# GSM.net
KiCad netlist of a schematic drawn in Altium Designer
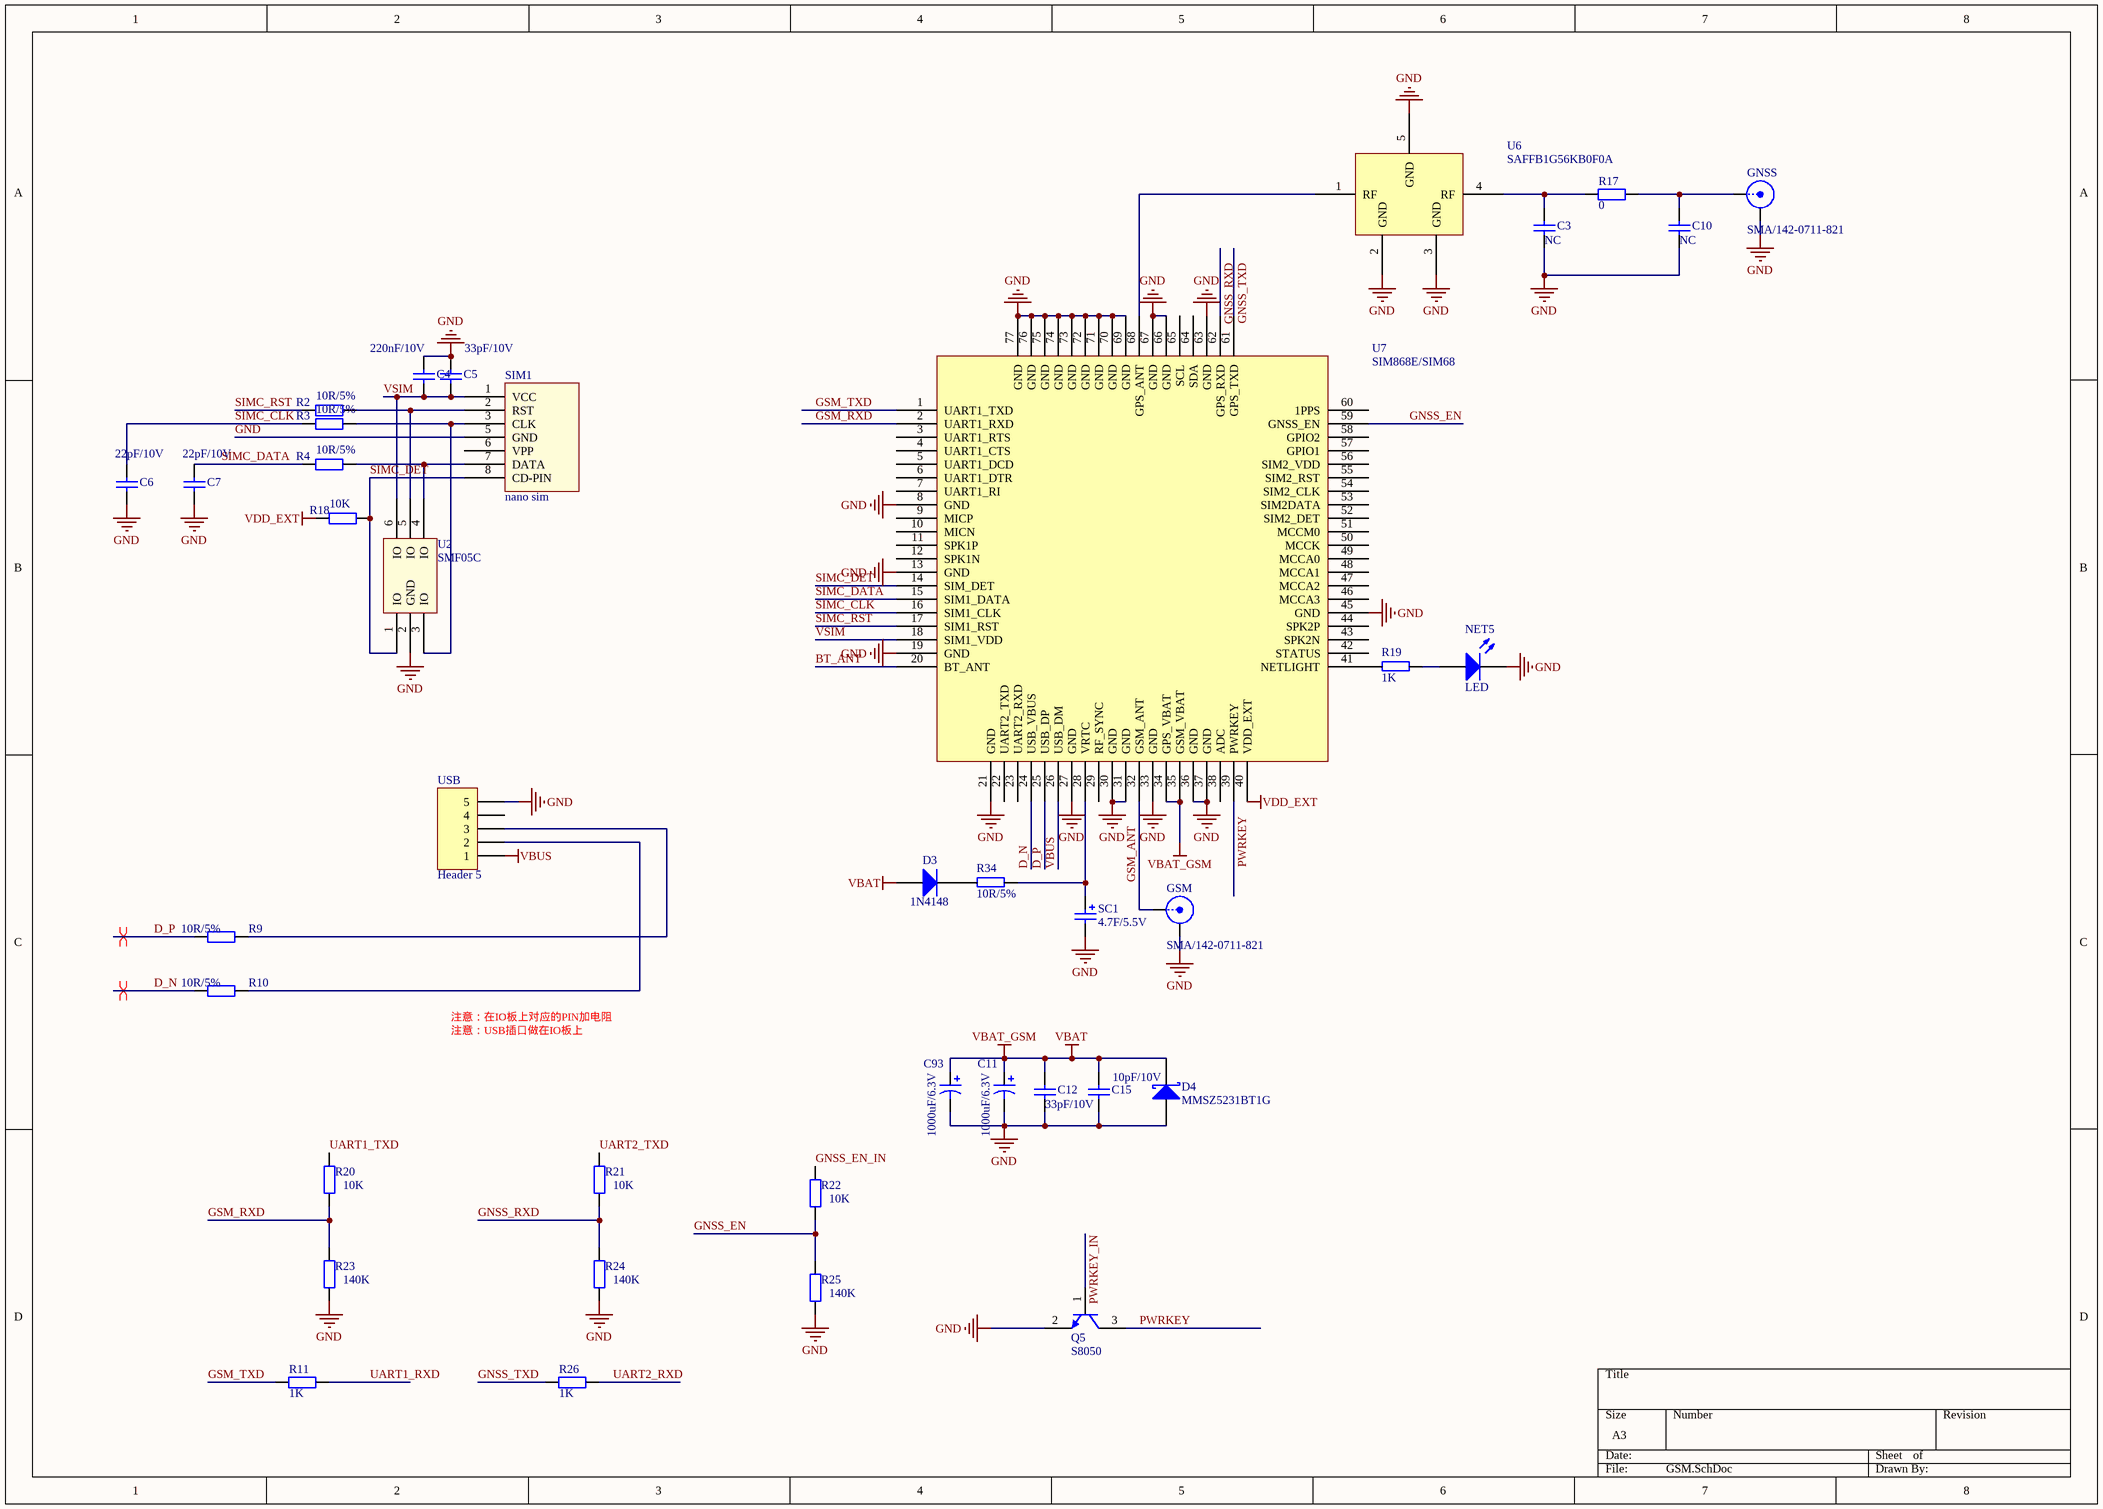
[diagram p0: GSM.SchDoc]

(export (version "E")
  (design (tool "Eeschema 10.0.6"))
  (components
    (comp (ref "C3")
      (value "NC")
      (footprint "0603C")
      (description "Capacitor")
      (fields (field (name "PUBLISHER") "Altium Limited"))
      (libsource (lib "Miscellaneous Devices") (part "Cap"))
    )
    (comp (ref "C4")
      (value "220nF/10V")
      (footprint "0603C")
      (description "Capacitor")
      (fields (field (name "PUBLISHER") "Altium Limited"))
      (libsource (lib "Miscellaneous Devices") (part "Cap"))
    )
    (comp (ref "C5")
      (value "33pF/10V")
      (footprint "0603C")
      (description "Capacitor")
      (fields (field (name "PUBLISHER") "Altium Limited"))
      (libsource (lib "Miscellaneous Devices") (part "Cap"))
    )
    (comp (ref "C6")
      (value "22pF/10V")
      (footprint "0603C")
      (description "Capacitor")
      (fields (field (name "PUBLISHER") "Altium Limited"))
      (libsource (lib "Miscellaneous Devices") (part "Cap"))
    )
    (comp (ref "C7")
      (value "22pF/10V")
      (footprint "0603C")
      (description "Capacitor")
      (fields (field (name "PUBLISHER") "Altium Limited"))
      (libsource (lib "Miscellaneous Devices") (part "Cap"))
    )
    (comp (ref "C10")
      (value "NC")
      (footprint "0603C")
      (description "Capacitor")
      (fields (field (name "PUBLISHER") "Altium Limited"))
      (libsource (lib "Miscellaneous Devices") (part "Cap"))
    )
    (comp (ref "C11")
      (value "1000uF/6.3V")
      (footprint "7343")
      (description "Polarized Capacitor (Radial)")
      (fields (field (name "PUBLISHER") "Altium Limited"))
      (libsource (lib "Miscellaneous Devices") (part "Cap Pol1"))
    )
    (comp (ref "C12")
      (value "33pF/10V")
      (footprint "0603C")
      (description "Capacitor")
      (fields (field (name "PUBLISHER") "Altium Limited"))
      (libsource (lib "Miscellaneous Devices") (part "Cap"))
    )
    (comp (ref "C15")
      (value "10pF/10V")
      (footprint "0603C")
      (description "Capacitor")
      (fields (field (name "PUBLISHER") "Altium Limited"))
      (libsource (lib "Miscellaneous Devices") (part "Cap"))
    )
    (comp (ref "C93")
      (value "1000uF/6.3V")
      (footprint "7343")
      (description "Polarized Capacitor (Radial)")
      (fields (field (name "PUBLISHER") "Altium Limited"))
      (libsource (lib "Miscellaneous Devices") (part "Cap Pol1"))
    )
    (comp (ref "D3")
      (value "1N4148")
      (footprint "LL34")
      (description "High Conductance Fast Diode")
      (fields (field (name "PUBLISHER") "Altium Limited"))
      (libsource (lib "Miscellaneous Devices") (part "Diode 1N4148"))
    )
    (comp (ref "D4")
      (value "MMSZ5231BT1G")
      (footprint "SOD123")
      (description "Schottky Rectifier")
      (fields (field (name "PUBLISHER") "Altium Limited"))
      (libsource (lib "Miscellaneous Devices") (part "Diode 10TQ040"))
    )
    (comp (ref "GNSS")
      (value "SMA/142-0711-821")
      (footprint "SMA END LAUNCH JACK RECEPTACLE SHORT")
      (description "SMA Straight Connector")
      (fields (field (name "PUBLISHER") "Altium Limited"))
      (libsource (lib "SX1276_e266v02a") (part "SMA"))
    )
    (comp (ref "GSM")
      (value "SMA/142-0711-821")
      (footprint "SMA END LAUNCH JACK RECEPTACLE SHORT")
      (description "SMA Straight Connector")
      (fields (field (name "PUBLISHER") "Altium Limited"))
      (libsource (lib "SX1276_e266v02a") (part "SMA"))
    )
    (comp (ref "NET5")
      (value "LED")
      (footprint "0603LED")
      (description "Typical RED, GREEN, YELLOW, AMBER GaAs LED")
      (fields (field (name "PUBLISHER") "Altium Limited"))
      (libsource (lib "SIM800C 原理图库") (part "LED2"))
    )
    (comp (ref "Q5") (value "S8050") (footprint "SOT23-3") (libsource (lib "Schlib1") (part "NPN")))
    (comp (ref "R2")
      (value "10R/5%")
      (footprint "0603R")
      (description "Resistor")
      (fields (field (name "PUBLISHER") "Altium Limited"))
      (libsource (lib "") (part "Res2_1"))
    )
    (comp (ref "R3")
      (value "10R/5%")
      (footprint "0603R")
      (description "Resistor")
      (fields (field (name "PUBLISHER") "Altium Limited"))
      (libsource (lib "") (part "Res2_1"))
    )
    (comp (ref "R4")
      (value "10R/5%")
      (footprint "0603R")
      (description "Resistor")
      (fields (field (name "PUBLISHER") "Altium Limited"))
      (libsource (lib "") (part "Res2_1"))
    )
    (comp (ref "R9")
      (value "10R/5%")
      (footprint "0603R")
      (description "Resistor SMD - IEC symbol version")
      (libsource (lib "SX1276_e266v02a") (part "Resistor"))
    )
    (comp (ref "R10")
      (value "10R/5%")
      (footprint "0603R")
      (description "Resistor SMD - IEC symbol version")
      (libsource (lib "SX1276_e266v02a") (part "Resistor"))
    )
    (comp (ref "R11")
      (value "1K")
      (footprint "0603R")
      (description "Resistor")
      (fields (field (name "PUBLISHER") "Altium Limited"))
      (libsource (lib "") (part "Res2_2"))
    )
    (comp (ref "R17")
      (value "0")
      (footprint "0603R")
      (description "Resistor")
      (fields (field (name "PUBLISHER") "Altium Limited"))
      (libsource (lib "") (part "Res2_2"))
    )
    (comp (ref "R18")
      (value "10K")
      (footprint "0603R")
      (description "Resistor")
      (fields (field (name "PUBLISHER") "Altium Limited"))
      (libsource (lib "") (part "Res2_1"))
    )
    (comp (ref "R19") (value "1K") (footprint "0603r") (libsource (lib "SIM800C 原理图库") (part "R")))
    (comp (ref "R20")
      (value "10K")
      (footprint "0603R")
      (description "Resistor")
      (fields (field (name "PUBLISHER") "Altium Limited"))
      (libsource (lib "Miscellaneous Devices") (part "Res2"))
    )
    (comp (ref "R21")
      (value "10K")
      (footprint "0603R")
      (description "Resistor")
      (fields (field (name "PUBLISHER") "Altium Limited"))
      (libsource (lib "Miscellaneous Devices") (part "Res2"))
    )
    (comp (ref "R22")
      (value "10K")
      (footprint "0603R")
      (description "Resistor")
      (fields (field (name "PUBLISHER") "Altium Limited"))
      (libsource (lib "Miscellaneous Devices") (part "Res2"))
    )
    (comp (ref "R23")
      (value "140K")
      (footprint "0603R")
      (description "Resistor")
      (fields (field (name "PUBLISHER") "Altium Limited"))
      (libsource (lib "Miscellaneous Devices") (part "Res2"))
    )
    (comp (ref "R24")
      (value "140K")
      (footprint "0603R")
      (description "Resistor")
      (fields (field (name "PUBLISHER") "Altium Limited"))
      (libsource (lib "Miscellaneous Devices") (part "Res2"))
    )
    (comp (ref "R25")
      (value "140K")
      (footprint "0603R")
      (description "Resistor")
      (fields (field (name "PUBLISHER") "Altium Limited"))
      (libsource (lib "Miscellaneous Devices") (part "Res2"))
    )
    (comp (ref "R26")
      (value "1K")
      (footprint "0603R")
      (description "Resistor")
      (fields (field (name "PUBLISHER") "Altium Limited"))
      (libsource (lib "") (part "Res2_2"))
    )
    (comp (ref "R34") (value "10R/5%") (footprint "0603r") (libsource (lib "SIM800C 原理图库") (part "R")))
    (comp (ref "SC1")
      (value "4.7F/5.5V")
      (footprint "SF-13.5*6.5")
      (description "Polarized Capacitor (Axial)")
      (fields (field (name "PUBLISHER") "Altium Limited"))
      (libsource (lib "Miscellaneous Devices") (part "Cap Pol2"))
    )
    (comp (ref "SIM1") (value "nano sim") (footprint "Nano SIM") (libsource (lib "lm") (part "nano sim")))
    (comp (ref "U2") (value "SMF05C") (footprint "SC70-6L") (libsource (lib "lm") (part "SMF05C")))
    (comp (ref "U6")
      (value "SAFFB1G56KB0F0A")
      (footprint "SAFFB1G56KB0F0A")
      (libsource (lib "stm32") (part "SAFFB1G56KBOFA"))
    )
    (comp (ref "U7")
      (value "SIM868E/SIM68")
      (footprint "SIM868")
      (libsource (lib "stm32") (part "SIM868E/SIM868"))
    )
    (comp (ref "USB")
      (value "Header 5")
      (footprint "Micro_USB_PH")
      (description "Header, 5-Pin")
      (fields (field (name "PUBLISHER") "Altium Limited"))
      (libsource (lib "Miscellaneous Connectors") (part "Header 5"))
    )
  )
  (nets
    (net (code "1") (name "/BT_ANT") (class "Default")
      (node (ref "U7") (pin "20") (pinfunction "BT_ANT_20") (pintype "passive"))
    )
    (net (code "2") (name "/D_N") (class "Default")
      (node (ref "R10") (pin "1") (pinfunction "1_1") (pintype "passive"))
      (node (ref "U7") (pin "24") (pinfunction "USB_VBUS_24") (pintype "passive"))
    )
    (net (code "3") (name "/D_P") (class "Default")
      (node (ref "R9") (pin "1") (pinfunction "1_1") (pintype "passive"))
      (node (ref "U7") (pin "25") (pinfunction "USB_DP_25") (pintype "passive"))
    )
    (net (code "4") (name "/GNSS_EN") (class "Default")
      (node (ref "R22") (pin "2") (pinfunction "2_2") (pintype "passive"))
      (node (ref "R25") (pin "1") (pinfunction "1_1") (pintype "passive"))
      (node (ref "U7") (pin "59") (pinfunction "GNSS_EN_59") (pintype "passive"))
    )
    (net (code "5") (name "/GNSS_EN_IN") (class "Default")
      (node (ref "R22") (pin "1") (pinfunction "1_1") (pintype "passive"))
    )
    (net (code "6") (name "/GNSS_RXD") (class "Default")
      (node (ref "R21") (pin "2") (pinfunction "2_2") (pintype "passive"))
      (node (ref "R24") (pin "1") (pinfunction "1_1") (pintype "passive"))
      (node (ref "U7") (pin "62") (pinfunction "GPS_RXD_62") (pintype "passive"))
    )
    (net (code "7") (name "/GNSS_TXD") (class "Default")
      (node (ref "R26") (pin "1") (pinfunction "1_1") (pintype "passive"))
      (node (ref "U7") (pin "61") (pinfunction "GPS_TXD_61") (pintype "passive"))
    )
    (net (code "8") (name "/GSM_ANT") (class "Default")
      (node (ref "GSM") (pin "1") (pinfunction "Signal_1") (pintype "passive"))
      (node (ref "U7") (pin "32") (pinfunction "GSM_ANT_32") (pintype "passive"))
    )
    (net (code "9") (name "/GSM_RXD") (class "Default")
      (node (ref "R20") (pin "2") (pinfunction "2_2") (pintype "passive"))
      (node (ref "R23") (pin "1") (pinfunction "1_1") (pintype "passive"))
      (node (ref "U7") (pin "2") (pinfunction "UART1_RXD_2") (pintype "passive"))
    )
    (net (code "10") (name "/GSM_TXD") (class "Default")
      (node (ref "R11") (pin "1") (pinfunction "1_1") (pintype "passive"))
      (node (ref "U7") (pin "1") (pinfunction "UART1_TXD_1") (pintype "passive"))
    )
    (net (code "11") (name "/PWRKEY") (class "Default")
      (node (ref "Q5") (pin "3") (pinfunction "C_3") (pintype "passive"))
      (node (ref "U7") (pin "39") (pinfunction "PWRKEY_39") (pintype "passive"))
    )
    (net (code "12") (name "/PWRKEY_IN") (class "Default")
      (node (ref "Q5") (pin "1") (pinfunction "B_1") (pintype "passive"))
    )
    (net (code "13") (name "/SIMC_CLK") (class "Default")
      (node (ref "C6") (pin "1") (pinfunction "1_1") (pintype "passive"))
      (node (ref "R3") (pin "2") (pinfunction "2_2") (pintype "passive"))
      (node (ref "U7") (pin "16") (pinfunction "SIM1_CLK_16") (pintype "passive"))
    )
    (net (code "14") (name "/SIMC_DATA") (class "Default")
      (node (ref "C7") (pin "1") (pinfunction "1_1") (pintype "passive"))
      (node (ref "R4") (pin "2") (pinfunction "2_2") (pintype "passive"))
      (node (ref "U7") (pin "15") (pinfunction "SIM1_DATA_15") (pintype "passive"))
    )
    (net (code "15") (name "/SIMC_DET") (class "Default")
      (node (ref "R18") (pin "1") (pinfunction "1_1") (pintype "passive"))
      (node (ref "SIM1") (pin "8") (pinfunction "CD-PIN_8") (pintype "passive"))
      (node (ref "U2") (pin "1") (pinfunction "IO_1") (pintype "passive"))
      (node (ref "U7") (pin "14") (pinfunction "SIM_DET_14") (pintype "passive"))
    )
    (net (code "16") (name "/SIMC_RST") (class "Default")
      (node (ref "R2") (pin "2") (pinfunction "2_2") (pintype "passive"))
      (node (ref "U7") (pin "17") (pinfunction "SIM1_RST_17") (pintype "passive"))
    )
    (net (code "17") (name "/UART1_RXD") (class "Default")
      (node (ref "R11") (pin "2") (pinfunction "2_2") (pintype "passive"))
    )
    (net (code "18") (name "/UART1_TXD") (class "Default")
      (node (ref "R20") (pin "1") (pinfunction "1_1") (pintype "passive"))
    )
    (net (code "19") (name "/UART2_RXD") (class "Default")
      (node (ref "R26") (pin "2") (pinfunction "2_2") (pintype "passive"))
    )
    (net (code "20") (name "/UART2_TXD") (class "Default")
      (node (ref "R21") (pin "1") (pinfunction "1_1") (pintype "passive"))
    )
    (net (code "21") (name "/VSIM") (class "Default")
      (node (ref "C4") (pin "2") (pinfunction "2_2") (pintype "passive"))
      (node (ref "C5") (pin "2") (pinfunction "2_2") (pintype "passive"))
      (node (ref "SIM1") (pin "1") (pinfunction "VCC_1") (pintype "passive"))
      (node (ref "U2") (pin "6") (pinfunction "IO_6") (pintype "passive"))
      (node (ref "U7") (pin "18") (pinfunction "SIM1_VDD_18") (pintype "passive"))
    )
    (net (code "22") (name "GND") (class "Default")
      (node (ref "C10") (pin "2") (pinfunction "2_2") (pintype "passive"))
      (node (ref "C11") (pin "2") (pinfunction "2_2") (pintype "passive"))
      (node (ref "C12") (pin "2") (pinfunction "2_2") (pintype "passive"))
      (node (ref "C15") (pin "2") (pinfunction "2_2") (pintype "passive"))
      (node (ref "C3") (pin "2") (pinfunction "2_2") (pintype "passive"))
      (node (ref "C4") (pin "1") (pinfunction "1_1") (pintype "passive"))
      (node (ref "C5") (pin "1") (pinfunction "1_1") (pintype "passive"))
      (node (ref "C6") (pin "2") (pinfunction "2_2") (pintype "passive"))
      (node (ref "C7") (pin "2") (pinfunction "2_2") (pintype "passive"))
      (node (ref "C93") (pin "2") (pinfunction "2_2") (pintype "passive"))
      (node (ref "D4") (pin "A") (pinfunction "A_A") (pintype "passive"))
      (node (ref "GNSS") (pin "2") (pinfunction "GND_2") (pintype "passive"))
      (node (ref "GSM") (pin "2") (pinfunction "GND_2") (pintype "passive"))
      (node (ref "NET5") (pin "2") (pinfunction "K_2") (pintype "passive"))
      (node (ref "Q5") (pin "2") (pinfunction "E_2") (pintype "passive"))
      (node (ref "R23") (pin "2") (pinfunction "2_2") (pintype "passive"))
      (node (ref "R24") (pin "2") (pinfunction "2_2") (pintype "passive"))
      (node (ref "R25") (pin "2") (pinfunction "2_2") (pintype "passive"))
      (node (ref "SC1") (pin "2") (pinfunction "2_2") (pintype "passive"))
      (node (ref "SIM1") (pin "5") (pinfunction "GND_5") (pintype "passive"))
      (node (ref "U2") (pin "2") (pinfunction "GND_2") (pintype "passive"))
      (node (ref "U6") (pin "2") (pinfunction "GND_2") (pintype "passive"))
      (node (ref "U6") (pin "3") (pinfunction "GND_3") (pintype "passive"))
      (node (ref "U6") (pin "5") (pinfunction "GND_5") (pintype "passive"))
      (node (ref "U7") (pin "13") (pinfunction "GND_13") (pintype "passive"))
      (node (ref "U7") (pin "19") (pinfunction "GND_19") (pintype "passive"))
      (node (ref "U7") (pin "21") (pinfunction "GND_21") (pintype "passive"))
      (node (ref "U7") (pin "27") (pinfunction "GND_27") (pintype "passive"))
      (node (ref "U7") (pin "30") (pinfunction "GND_30") (pintype "passive"))
      (node (ref "U7") (pin "31") (pinfunction "GND_31") (pintype "passive"))
      (node (ref "U7") (pin "33") (pinfunction "GND_33") (pintype "passive"))
      (node (ref "U7") (pin "36") (pinfunction "GND_36") (pintype "passive"))
      (node (ref "U7") (pin "37") (pinfunction "GND_37") (pintype "passive"))
      (node (ref "U7") (pin "45") (pinfunction "GND_45") (pintype "passive"))
      (node (ref "U7") (pin "63") (pinfunction "GND_63") (pintype "passive"))
      (node (ref "U7") (pin "66") (pinfunction "GND_66") (pintype "passive"))
      (node (ref "U7") (pin "67") (pinfunction "GND_67") (pintype "passive"))
      (node (ref "U7") (pin "69") (pinfunction "GND_69") (pintype "passive"))
      (node (ref "U7") (pin "70") (pinfunction "GND_70") (pintype "passive"))
      (node (ref "U7") (pin "71") (pinfunction "GND_71") (pintype "passive"))
      (node (ref "U7") (pin "72") (pinfunction "GND_72") (pintype "passive"))
      (node (ref "U7") (pin "73") (pinfunction "GND_73") (pintype "passive"))
      (node (ref "U7") (pin "74") (pinfunction "GND_74") (pintype "passive"))
      (node (ref "U7") (pin "75") (pinfunction "GND_75") (pintype "passive"))
      (node (ref "U7") (pin "76") (pinfunction "GND_76") (pintype "passive"))
      (node (ref "U7") (pin "77") (pinfunction "GND_77") (pintype "passive"))
      (node (ref "U7") (pin "8") (pinfunction "GND_8") (pintype "passive"))
      (node (ref "USB") (pin "5") (pinfunction "5_5") (pintype "passive"))
    )
    (net (code "23") (name "Net-(C3-Pad1)") (class "Default")
      (node (ref "C3") (pin "1") (pinfunction "1_1") (pintype "passive"))
      (node (ref "R17") (pin "1") (pinfunction "1_1") (pintype "passive"))
      (node (ref "U6") (pin "4") (pinfunction "RF_4") (pintype "passive"))
    )
    (net (code "24") (name "Net-(D3-K)") (class "Default")
      (node (ref "D3") (pin "2") (pinfunction "K_2") (pintype "passive"))
      (node (ref "R34") (pin "2") (pintype "passive"))
    )
    (net (code "25") (name "Net-(GNSS-Signal)") (class "Default")
      (node (ref "C10") (pin "1") (pinfunction "1_1") (pintype "passive"))
      (node (ref "GNSS") (pin "1") (pinfunction "Signal_1") (pintype "passive"))
      (node (ref "R17") (pin "2") (pinfunction "2_2") (pintype "passive"))
    )
    (net (code "26") (name "Net-(NET5-A)") (class "Default")
      (node (ref "NET5") (pin "1") (pinfunction "A_1") (pintype "passive"))
      (node (ref "R19") (pin "1") (pintype "passive"))
    )
    (net (code "27") (name "Net-(R9-Pad2)") (class "Default")
      (node (ref "R9") (pin "2") (pinfunction "2_2") (pintype "passive"))
      (node (ref "USB") (pin "3") (pinfunction "3_3") (pintype "passive"))
    )
    (net (code "28") (name "Net-(R10-Pad2)") (class "Default")
      (node (ref "R10") (pin "2") (pinfunction "2_2") (pintype "passive"))
      (node (ref "USB") (pin "2") (pinfunction "2_2") (pintype "passive"))
    )
    (net (code "29") (name "Net-(SIM1-CLK)") (class "Default")
      (node (ref "R3") (pin "1") (pinfunction "1_1") (pintype "passive"))
      (node (ref "SIM1") (pin "3") (pinfunction "CLK_3") (pintype "passive"))
      (node (ref "U2") (pin "3") (pinfunction "IO_3") (pintype "passive"))
    )
    (net (code "30") (name "Net-(SIM1-DATA)") (class "Default")
      (node (ref "R4") (pin "1") (pinfunction "1_1") (pintype "passive"))
      (node (ref "SIM1") (pin "7") (pinfunction "DATA_7") (pintype "passive"))
      (node (ref "U2") (pin "4") (pinfunction "IO_4") (pintype "passive"))
    )
    (net (code "31") (name "Net-(SIM1-RST)") (class "Default")
      (node (ref "R2") (pin "1") (pinfunction "1_1") (pintype "passive"))
      (node (ref "SIM1") (pin "2") (pinfunction "RST_2") (pintype "passive"))
      (node (ref "U2") (pin "5") (pinfunction "IO_5") (pintype "passive"))
    )
    (net (code "32") (name "Net-(U7-GPS_ANT)") (class "Default")
      (node (ref "U6") (pin "1") (pinfunction "RF_1") (pintype "passive"))
      (node (ref "U7") (pin "68") (pinfunction "GPS_ANT_68") (pintype "passive"))
    )
    (net (code "33") (name "Net-(U7-NETLIGHT)") (class "Default")
      (node (ref "R19") (pin "2") (pintype "passive"))
      (node (ref "U7") (pin "41") (pinfunction "NETLIGHT_41") (pintype "passive"))
    )
    (net (code "34") (name "Net-(U7-VRTC)") (class "Default")
      (node (ref "R34") (pin "1") (pintype "passive"))
      (node (ref "SC1") (pin "1") (pinfunction "1_1") (pintype "passive"))
      (node (ref "U7") (pin "28") (pinfunction "VRTC_28") (pintype "passive"))
    )
    (net (code "35") (name "VBAT") (class "Default")
      (node (ref "C11") (pin "1") (pinfunction "1_1") (pintype "passive"))
      (node (ref "C12") (pin "1") (pinfunction "1_1") (pintype "passive"))
      (node (ref "C15") (pin "1") (pinfunction "1_1") (pintype "passive"))
      (node (ref "C93") (pin "1") (pinfunction "1_1") (pintype "passive"))
      (node (ref "D3") (pin "1") (pinfunction "A_1") (pintype "passive"))
      (node (ref "D4") (pin "K") (pinfunction "K_K") (pintype "passive"))
      (node (ref "U7") (pin "34") (pinfunction "GPS_VBAT_34") (pintype "passive"))
      (node (ref "U7") (pin "35") (pinfunction "GSM_VBAT_35") (pintype "passive"))
    )
    (net (code "36") (name "VBUS") (class "Default")
      (node (ref "U7") (pin "26") (pinfunction "USB_DM_26") (pintype "passive"))
      (node (ref "USB") (pin "1") (pinfunction "1_1") (pintype "passive"))
    )
    (net (code "37") (name "VDD_EXT") (class "Default")
      (node (ref "R18") (pin "2") (pinfunction "2_2") (pintype "passive"))
      (node (ref "U7") (pin "40") (pinfunction "VDD_EXT_40") (pintype "passive"))
    )
    (net (code "38") (name "unconnected-(SIM1-VPP-Pad6)") (class "Default")
      (node (ref "SIM1") (pin "6") (pinfunction "VPP_6") (pintype "passive"))
    )
    (net (code "39") (name "unconnected-(U7-1PPS-Pad60)") (class "Default")
      (node (ref "U7") (pin "60") (pinfunction "1PPS_60") (pintype "passive"))
    )
    (net (code "40") (name "unconnected-(U7-ADC-Pad38)") (class "Default")
      (node (ref "U7") (pin "38") (pinfunction "ADC_38") (pintype "passive"))
    )
    (net (code "41") (name "unconnected-(U7-GPIO1-Pad57)") (class "Default")
      (node (ref "U7") (pin "57") (pinfunction "GPIO1_57") (pintype "passive"))
    )
    (net (code "42") (name "unconnected-(U7-GPIO2-Pad58)") (class "Default")
      (node (ref "U7") (pin "58") (pinfunction "GPIO2_58") (pintype "passive"))
    )
    (net (code "43") (name "unconnected-(U7-MCCA0-Pad49)") (class "Default")
      (node (ref "U7") (pin "49") (pinfunction "MCCA0_49") (pintype "passive"))
    )
    (net (code "44") (name "unconnected-(U7-MCCA1-Pad48)") (class "Default")
      (node (ref "U7") (pin "48") (pinfunction "MCCA1_48") (pintype "passive"))
    )
    (net (code "45") (name "unconnected-(U7-MCCA2-Pad47)") (class "Default")
      (node (ref "U7") (pin "47") (pinfunction "MCCA2_47") (pintype "passive"))
    )
    (net (code "46") (name "unconnected-(U7-MCCA3-Pad46)") (class "Default")
      (node (ref "U7") (pin "46") (pinfunction "MCCA3_46") (pintype "passive"))
    )
    (net (code "47") (name "unconnected-(U7-MCCK-Pad50)") (class "Default")
      (node (ref "U7") (pin "50") (pinfunction "MCCK_50") (pintype "passive"))
    )
    (net (code "48") (name "unconnected-(U7-MCCM0-Pad51)") (class "Default")
      (node (ref "U7") (pin "51") (pinfunction "MCCM0_51") (pintype "passive"))
    )
    (net (code "49") (name "unconnected-(U7-MICN-Pad10)") (class "Default")
      (node (ref "U7") (pin "10") (pinfunction "MICN_10") (pintype "passive"))
    )
    (net (code "50") (name "unconnected-(U7-MICP-Pad9)") (class "Default")
      (node (ref "U7") (pin "9") (pinfunction "MICP_9") (pintype "passive"))
    )
    (net (code "51") (name "unconnected-(U7-RF_SYNC-Pad29)") (class "Default")
      (node (ref "U7") (pin "29") (pinfunction "RF_SYNC_29") (pintype "passive"))
    )
    (net (code "52") (name "unconnected-(U7-SCL-Pad65)") (class "Default")
      (node (ref "U7") (pin "65") (pinfunction "SCL_65") (pintype "passive"))
    )
    (net (code "53") (name "unconnected-(U7-SDA-Pad64)") (class "Default")
      (node (ref "U7") (pin "64") (pinfunction "SDA_64") (pintype "passive"))
    )
    (net (code "54") (name "unconnected-(U7-SIM2DATA-Pad53)") (class "Default")
      (node (ref "U7") (pin "53") (pinfunction "SIM2DATA_53") (pintype "passive"))
    )
    (net (code "55") (name "unconnected-(U7-SIM2_CLK-Pad54)") (class "Default")
      (node (ref "U7") (pin "54") (pinfunction "SIM2_CLK_54") (pintype "passive"))
    )
    (net (code "56") (name "unconnected-(U7-SIM2_DET-Pad52)") (class "Default")
      (node (ref "U7") (pin "52") (pinfunction "SIM2_DET_52") (pintype "passive"))
    )
    (net (code "57") (name "unconnected-(U7-SIM2_RST-Pad55)") (class "Default")
      (node (ref "U7") (pin "55") (pinfunction "SIM2_RST_55") (pintype "passive"))
    )
    (net (code "58") (name "unconnected-(U7-SIM2_VDD-Pad56)") (class "Default")
      (node (ref "U7") (pin "56") (pinfunction "SIM2_VDD_56") (pintype "passive"))
    )
    (net (code "59") (name "unconnected-(U7-SPK1N-Pad12)") (class "Default")
      (node (ref "U7") (pin "12") (pinfunction "SPK1N_12") (pintype "passive"))
    )
    (net (code "60") (name "unconnected-(U7-SPK1P-Pad11)") (class "Default")
      (node (ref "U7") (pin "11") (pinfunction "SPK1P_11") (pintype "passive"))
    )
    (net (code "61") (name "unconnected-(U7-SPK2N-Pad43)") (class "Default")
      (node (ref "U7") (pin "43") (pinfunction "SPK2N_43") (pintype "passive"))
    )
    (net (code "62") (name "unconnected-(U7-SPK2P-Pad44)") (class "Default")
      (node (ref "U7") (pin "44") (pinfunction "SPK2P_44") (pintype "passive"))
    )
    (net (code "63") (name "unconnected-(U7-STATUS-Pad42)") (class "Default")
      (node (ref "U7") (pin "42") (pinfunction "STATUS_42") (pintype "passive"))
    )
    (net (code "64") (name "unconnected-(U7-UART1_CTS-Pad4)") (class "Default")
      (node (ref "U7") (pin "4") (pinfunction "UART1_CTS_4") (pintype "passive"))
    )
    (net (code "65") (name "unconnected-(U7-UART1_DCD-Pad5)") (class "Default")
      (node (ref "U7") (pin "5") (pinfunction "UART1_DCD_5") (pintype "passive"))
    )
    (net (code "66") (name "unconnected-(U7-UART1_DTR-Pad6)") (class "Default")
      (node (ref "U7") (pin "6") (pinfunction "UART1_DTR_6") (pintype "passive"))
    )
    (net (code "67") (name "unconnected-(U7-UART1_RI-Pad7)") (class "Default")
      (node (ref "U7") (pin "7") (pinfunction "UART1_RI_7") (pintype "passive"))
    )
    (net (code "68") (name "unconnected-(U7-UART1_RTS-Pad3)") (class "Default")
      (node (ref "U7") (pin "3") (pinfunction "UART1_RTS_3") (pintype "passive"))
    )
    (net (code "69") (name "unconnected-(U7-UART2_RXD-Pad23)") (class "Default")
      (node (ref "U7") (pin "23") (pinfunction "UART2_RXD_23") (pintype "passive"))
    )
    (net (code "70") (name "unconnected-(U7-UART2_TXD-Pad22)") (class "Default")
      (node (ref "U7") (pin "22") (pinfunction "UART2_TXD_22") (pintype "passive"))
    )
    (net (code "71") (name "unconnected-(USB-Pad4)") (class "Default")
      (node (ref "USB") (pin "4") (pinfunction "4_4") (pintype "passive"))
    )
  )
)
